# ESC_v0_2.net
KiCad netlist of a schematic drawn in EAGLE
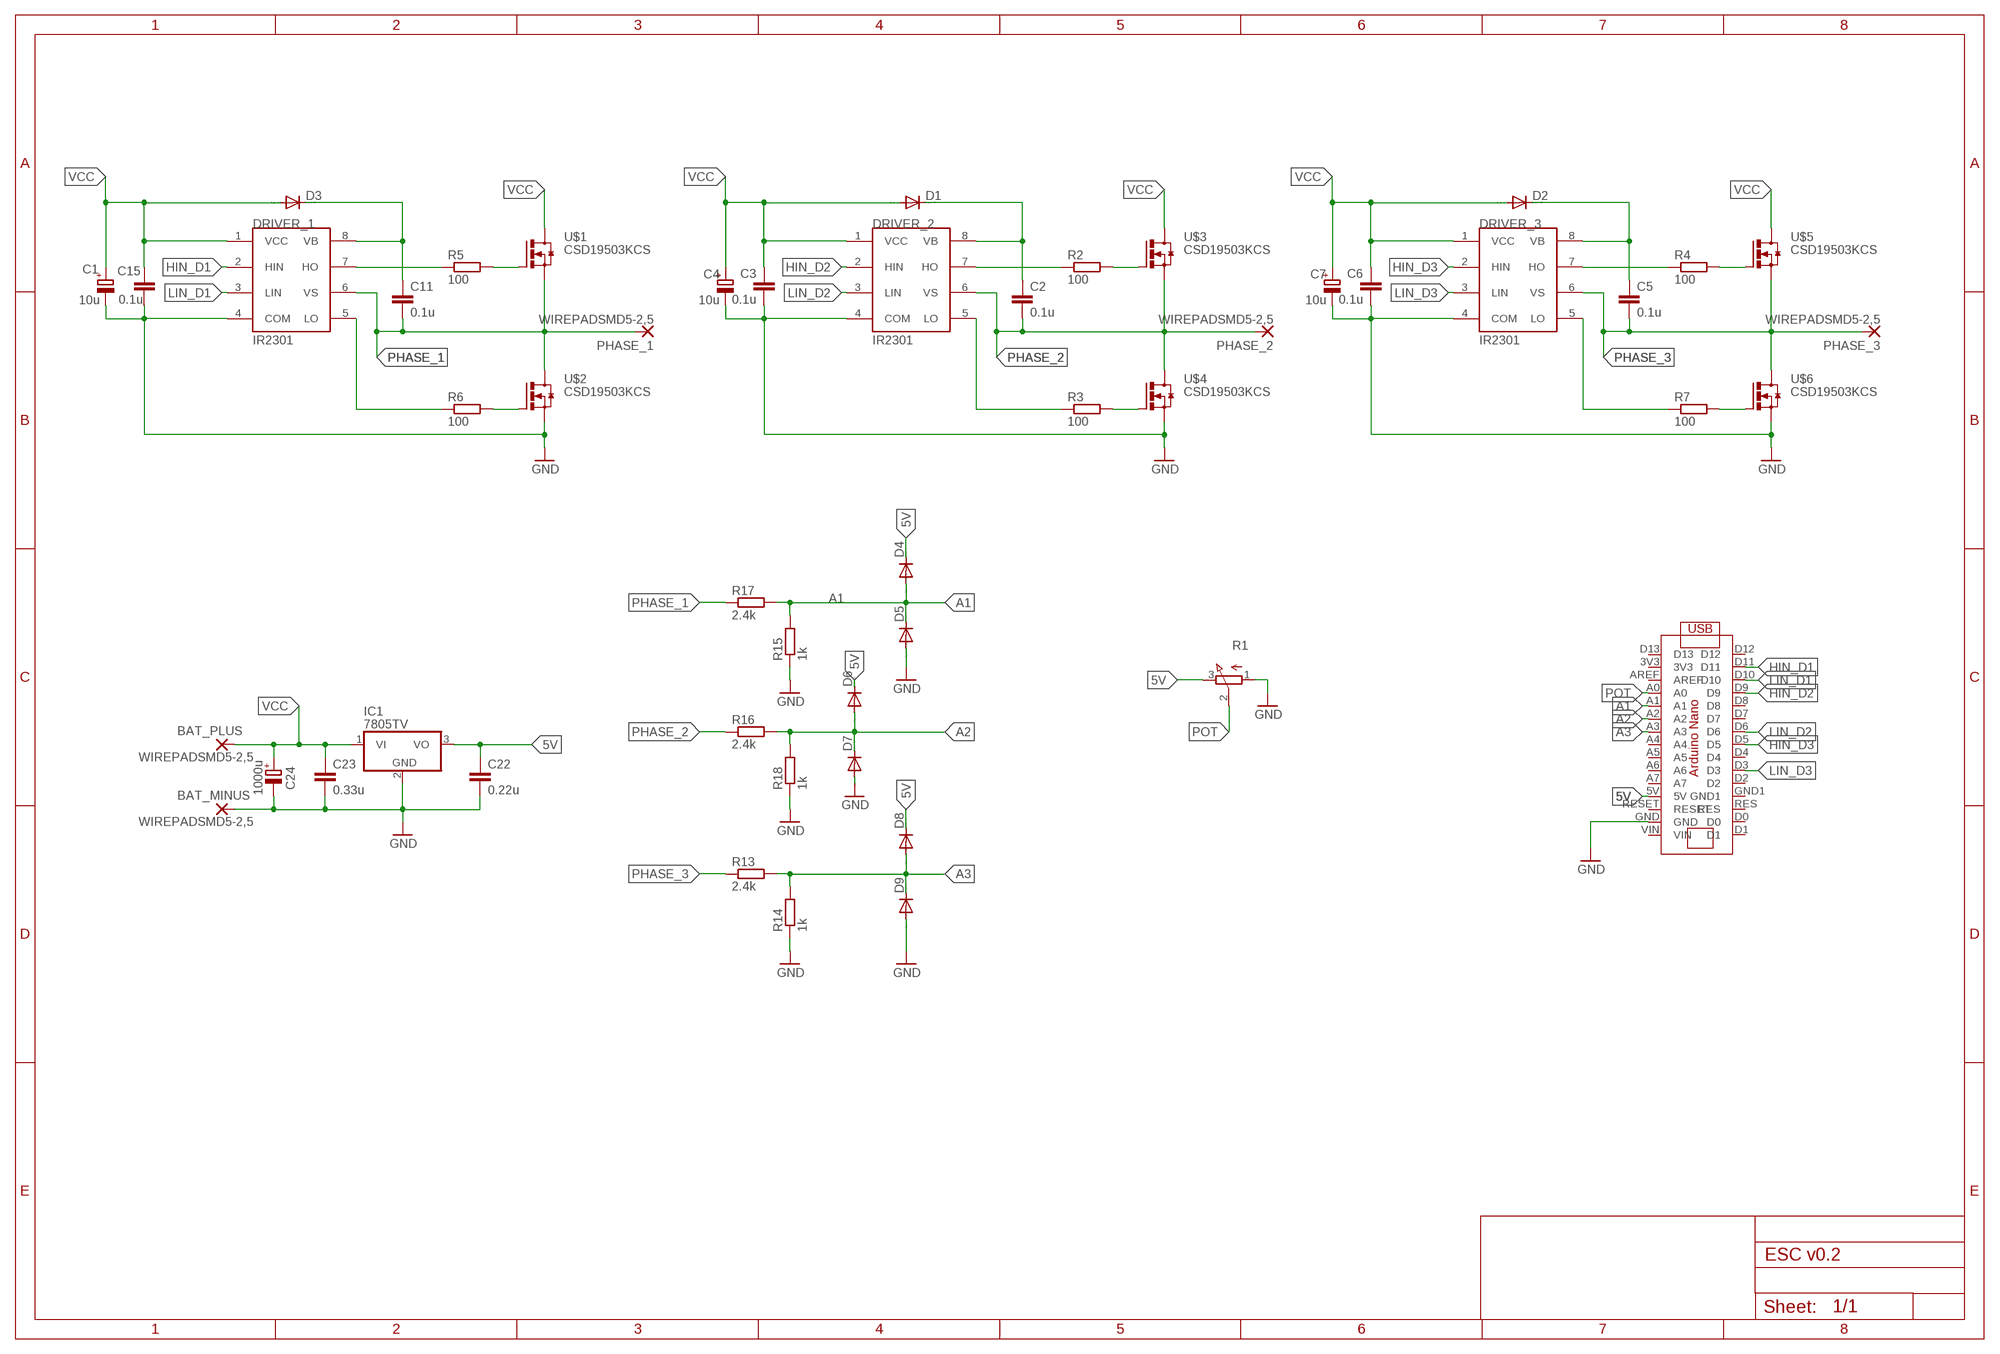
[diagram p0: schematic, sheet 1]

(export (version "E")
  (design (tool "Eeschema 10.0.6"))
  (components
    (comp (ref "BAT_MINUS")
      (value "WIREPADSMD5-2,5")
      (footprint "eagle-import:5-2,5")
      (libsource (lib "eagle-import") (part "WIREPADSMD5-2,5"))
    )
    (comp (ref "BAT_PLUS")
      (value "WIREPADSMD5-2,5")
      (footprint "eagle-import:5-2,5")
      (libsource (lib "eagle-import") (part "WIREPADSMD5-2,5"))
    )
    (comp (ref "C1")
      (value "10u")
      (footprint "eagle-import:153CLV-0605")
      (libsource (lib "eagle-import") (part "CPOL-EU153CLV-0605"))
    )
    (comp (ref "C2")
      (value "0.1u")
      (footprint "eagle-import:C1206")
      (libsource (lib "eagle-import") (part "CC1206"))
    )
    (comp (ref "C3")
      (value "0.1u")
      (footprint "eagle-import:C1206")
      (libsource (lib "eagle-import") (part "CC1206"))
    )
    (comp (ref "C4")
      (value "10u")
      (footprint "eagle-import:153CLV-0605")
      (libsource (lib "eagle-import") (part "CPOL-EU153CLV-0605"))
    )
    (comp (ref "C5")
      (value "0.1u")
      (footprint "eagle-import:C1206")
      (libsource (lib "eagle-import") (part "CC1206"))
    )
    (comp (ref "C6")
      (value "0.1u")
      (footprint "eagle-import:C1206")
      (libsource (lib "eagle-import") (part "CC1206"))
    )
    (comp (ref "C7")
      (value "10u")
      (footprint "eagle-import:153CLV-0605")
      (libsource (lib "eagle-import") (part "CPOL-EU153CLV-0605"))
    )
    (comp (ref "C11")
      (value "0.1u")
      (footprint "eagle-import:C1206")
      (libsource (lib "eagle-import") (part "CC1206"))
    )
    (comp (ref "C15")
      (value "0.1u")
      (footprint "eagle-import:C1206")
      (libsource (lib "eagle-import") (part "CC1206"))
    )
    (comp (ref "C22")
      (value "0.22u")
      (footprint "eagle-import:C1206")
      (libsource (lib "eagle-import") (part "CC1206"))
    )
    (comp (ref "C23")
      (value "0.33u")
      (footprint "eagle-import:C1206")
      (libsource (lib "eagle-import") (part "CC1206"))
    )
    (comp (ref "C24")
      (value "1000u")
      (footprint "eagle-import:E7,5-16")
      (libsource (lib "eagle-import") (part "CPOL-EUE7.5-16"))
    )
    (comp (ref "D1")
      (value "DIODE-DO41-10")
      (footprint "eagle-import:DO41-10")
      (libsource (lib "eagle-import") (part "DIODE-DO41-10"))
    )
    (comp (ref "D2")
      (value "DIODE-DO41-10")
      (footprint "eagle-import:DO41-10")
      (libsource (lib "eagle-import") (part "DIODE-DO41-10"))
    )
    (comp (ref "D3")
      (value "DIODE-DO41-10")
      (footprint "eagle-import:DO41-10")
      (libsource (lib "eagle-import") (part "DIODE-DO41-10"))
    )
    (comp (ref "D4")
      (value "DIODE-DO41-10")
      (footprint "eagle-import:DO41-10")
      (libsource (lib "eagle-import") (part "DIODE-DO41-10"))
    )
    (comp (ref "D5")
      (value "DIODE-DO41-10")
      (footprint "eagle-import:DO41-10")
      (libsource (lib "eagle-import") (part "DIODE-DO41-10"))
    )
    (comp (ref "D6")
      (value "DIODE-DO41-10")
      (footprint "eagle-import:DO41-10")
      (libsource (lib "eagle-import") (part "DIODE-DO41-10"))
    )
    (comp (ref "D7")
      (value "DIODE-DO41-10")
      (footprint "eagle-import:DO41-10")
      (libsource (lib "eagle-import") (part "DIODE-DO41-10"))
    )
    (comp (ref "D8")
      (value "DIODE-DO41-10")
      (footprint "eagle-import:DO41-10")
      (libsource (lib "eagle-import") (part "DIODE-DO41-10"))
    )
    (comp (ref "D9")
      (value "DIODE-DO41-10")
      (footprint "eagle-import:DO41-10")
      (libsource (lib "eagle-import") (part "DIODE-DO41-10"))
    )
    (comp (ref "DRIVER_1")
      (value "IR2301")
      (footprint "eagle-import:DIL08")
      (fields (field (name "MF") "Infineon"))
      (libsource (lib "eagle-import") (part "IR2301"))
    )
    (comp (ref "DRIVER_2")
      (value "IR2301")
      (footprint "eagle-import:DIL08")
      (fields (field (name "MF") "Infineon"))
      (libsource (lib "eagle-import") (part "IR2301"))
    )
    (comp (ref "DRIVER_3")
      (value "IR2301")
      (footprint "eagle-import:DIL08")
      (fields (field (name "MF") "Infineon"))
      (libsource (lib "eagle-import") (part "IR2301"))
    )
    (comp (ref "IC1")
      (value "7805TV")
      (footprint "eagle-import:TO220V")
      (libsource (lib "eagle-import") (part "78TV05"))
    )
    (comp (ref "PHASE_1")
      (value "WIREPADSMD5-2,5")
      (footprint "eagle-import:5-2,5")
      (libsource (lib "eagle-import") (part "WIREPADSMD5-2,5"))
    )
    (comp (ref "PHASE_2")
      (value "WIREPADSMD5-2,5")
      (footprint "eagle-import:5-2,5")
      (libsource (lib "eagle-import") (part "WIREPADSMD5-2,5"))
    )
    (comp (ref "PHASE_3")
      (value "WIREPADSMD5-2,5")
      (footprint "eagle-import:5-2,5")
      (libsource (lib "eagle-import") (part "WIREPADSMD5-2,5"))
    )
    (comp (ref "R1")
      (value "3RP/1610N")
      (footprint "eagle-import:3RP_1610N")
      (libsource (lib "eagle-import") (part "3RP/1610N"))
    )
    (comp (ref "R2")
      (value "100")
      (footprint "eagle-import:R1206")
      (libsource (lib "eagle-import") (part "R-EU_R1206"))
    )
    (comp (ref "R3")
      (value "100")
      (footprint "eagle-import:R1206")
      (libsource (lib "eagle-import") (part "R-EU_R1206"))
    )
    (comp (ref "R4")
      (value "100")
      (footprint "eagle-import:R1206")
      (libsource (lib "eagle-import") (part "R-EU_R1206"))
    )
    (comp (ref "R5")
      (value "100")
      (footprint "eagle-import:R1206")
      (libsource (lib "eagle-import") (part "R-EU_R1206"))
    )
    (comp (ref "R6")
      (value "100")
      (footprint "eagle-import:R1206")
      (libsource (lib "eagle-import") (part "R-EU_R1206"))
    )
    (comp (ref "R7")
      (value "100")
      (footprint "eagle-import:R1206")
      (libsource (lib "eagle-import") (part "R-EU_R1206"))
    )
    (comp (ref "R13")
      (value "2.4k")
      (footprint "eagle-import:R1206")
      (libsource (lib "eagle-import") (part "R-EU_R1206"))
    )
    (comp (ref "R14")
      (value "1k")
      (footprint "eagle-import:R1206")
      (libsource (lib "eagle-import") (part "R-EU_R1206"))
    )
    (comp (ref "R15")
      (value "1k")
      (footprint "eagle-import:R1206")
      (libsource (lib "eagle-import") (part "R-EU_R1206"))
    )
    (comp (ref "R16")
      (value "2.4k")
      (footprint "eagle-import:R1206")
      (libsource (lib "eagle-import") (part "R-EU_R1206"))
    )
    (comp (ref "R17")
      (value "2.4k")
      (footprint "eagle-import:R1206")
      (libsource (lib "eagle-import") (part "R-EU_R1206"))
    )
    (comp (ref "R18")
      (value "1k")
      (footprint "eagle-import:R1206")
      (libsource (lib "eagle-import") (part "R-EU_R1206"))
    )
    (comp (ref "U$1")
      (value "CSD19503KCS")
      (footprint "eagle-import:TO220BV")
      (fields (field (name "SPICEPREFIX") "M"))
      (libsource (lib "eagle-import") (part "CSD19503KCS"))
    )
    (comp (ref "U$2")
      (value "CSD19503KCS")
      (footprint "eagle-import:TO220BV")
      (libsource (lib "eagle-import") (part "CSD19503KCS"))
    )
    (comp (ref "U$3")
      (value "CSD19503KCS")
      (footprint "eagle-import:TO220BV")
      (libsource (lib "eagle-import") (part "CSD19503KCS"))
    )
    (comp (ref "U$4")
      (value "CSD19503KCS")
      (footprint "eagle-import:TO220BV")
      (libsource (lib "eagle-import") (part "CSD19503KCS"))
    )
    (comp (ref "U$5")
      (value "CSD19503KCS")
      (footprint "eagle-import:TO220BV")
      (libsource (lib "eagle-import") (part "CSD19503KCS"))
    )
    (comp (ref "U$6")
      (value "CSD19503KCS")
      (footprint "eagle-import:TO220BV")
      (libsource (lib "eagle-import") (part "CSD19503KCS"))
    )
    (comp (ref "U$7")
      (value "ARDUINO-NANO")
      (footprint "eagle-import:ARDUINO-NANO")
      (libsource (lib "eagle-import") (part "ARDUINO-NANO"))
    )
  )
  (nets
    (net (code "1") (name "/VB") (class "Default")
      (node (ref "C11") (pin "1") (pinfunction "1_1") (pintype "passive"))
      (node (ref "C2") (pin "1") (pinfunction "1_1") (pintype "passive"))
      (node (ref "C5") (pin "1") (pinfunction "1_1") (pintype "passive"))
      (node (ref "D1") (pin "C") (pinfunction "C_C") (pintype "passive"))
      (node (ref "D2") (pin "C") (pinfunction "C_C") (pintype "passive"))
      (node (ref "D3") (pin "C") (pinfunction "C_C") (pintype "passive"))
      (node (ref "DRIVER_1") (pin "8") (pinfunction "VB_8") (pintype "power_in"))
      (node (ref "DRIVER_2") (pin "8") (pinfunction "VB_8") (pintype "power_in"))
      (node (ref "DRIVER_3") (pin "8") (pinfunction "VB_8") (pintype "power_in"))
    )
    (net (code "2") (name "5V") (class "Default")
      (node (ref "C22") (pin "1") (pinfunction "1_1") (pintype "passive"))
      (node (ref "D4") (pin "C") (pinfunction "C_C") (pintype "passive"))
      (node (ref "D6") (pin "C") (pinfunction "C_C") (pintype "passive"))
      (node (ref "D8") (pin "C") (pinfunction "C_C") (pintype "passive"))
      (node (ref "IC1") (pin "3") (pinfunction "VO_3") (pintype "passive"))
      (node (ref "R1") (pin "3") (pinfunction "E_3") (pintype "passive"))
      (node (ref "U$7") (pin "5V") (pinfunction "5V_5V") (pintype "bidirectional"))
    )
    (net (code "3") (name "A1") (class "Default")
      (node (ref "D4") (pin "A") (pinfunction "A_A") (pintype "passive"))
      (node (ref "D5") (pin "C") (pinfunction "C_C") (pintype "passive"))
      (node (ref "R15") (pin "2") (pinfunction "2_2") (pintype "bidirectional"))
      (node (ref "R17") (pin "2") (pinfunction "2_2") (pintype "bidirectional"))
      (node (ref "U$7") (pin "A1") (pinfunction "A1_A1") (pintype "bidirectional"))
    )
    (net (code "4") (name "A2") (class "Default")
      (node (ref "D6") (pin "A") (pinfunction "A_A") (pintype "passive"))
      (node (ref "D7") (pin "C") (pinfunction "C_C") (pintype "passive"))
      (node (ref "R16") (pin "2") (pinfunction "2_2") (pintype "bidirectional"))
      (node (ref "R18") (pin "2") (pinfunction "2_2") (pintype "bidirectional"))
      (node (ref "U$7") (pin "A2") (pinfunction "A2_A2") (pintype "bidirectional"))
    )
    (net (code "5") (name "A3") (class "Default")
      (node (ref "D8") (pin "A") (pinfunction "A_A") (pintype "passive"))
      (node (ref "D9") (pin "C") (pinfunction "C_C") (pintype "passive"))
      (node (ref "R13") (pin "2") (pinfunction "2_2") (pintype "bidirectional"))
      (node (ref "R14") (pin "2") (pinfunction "2_2") (pintype "bidirectional"))
      (node (ref "U$7") (pin "A3") (pinfunction "A3_A3") (pintype "bidirectional"))
    )
    (net (code "6") (name "GND") (class "Default")
      (node (ref "BAT_MINUS") (pin "1") (pinfunction "P_1") (pintype "passive"))
      (node (ref "C1") (pin "-") (pinfunction "-_-") (pintype "passive"))
      (node (ref "C15") (pin "2") (pinfunction "2_2") (pintype "passive"))
      (node (ref "C22") (pin "2") (pinfunction "2_2") (pintype "passive"))
      (node (ref "C23") (pin "2") (pinfunction "2_2") (pintype "passive"))
      (node (ref "C24") (pin "-") (pinfunction "-_-") (pintype "passive"))
      (node (ref "C3") (pin "2") (pinfunction "2_2") (pintype "passive"))
      (node (ref "C4") (pin "-") (pinfunction "-_-") (pintype "passive"))
      (node (ref "C6") (pin "2") (pinfunction "2_2") (pintype "passive"))
      (node (ref "C7") (pin "-") (pinfunction "-_-") (pintype "passive"))
      (node (ref "D5") (pin "A") (pinfunction "A_A") (pintype "passive"))
      (node (ref "D7") (pin "A") (pinfunction "A_A") (pintype "passive"))
      (node (ref "D9") (pin "A") (pinfunction "A_A") (pintype "passive"))
      (node (ref "DRIVER_1") (pin "4") (pinfunction "COM_4") (pintype "power_in"))
      (node (ref "DRIVER_2") (pin "4") (pinfunction "COM_4") (pintype "power_in"))
      (node (ref "DRIVER_3") (pin "4") (pinfunction "COM_4") (pintype "power_in"))
      (node (ref "IC1") (pin "2") (pinfunction "GND_2") (pintype "passive"))
      (node (ref "R1") (pin "1") (pinfunction "A_1") (pintype "passive"))
      (node (ref "R14") (pin "1") (pinfunction "1_1") (pintype "bidirectional"))
      (node (ref "R15") (pin "1") (pinfunction "1_1") (pintype "bidirectional"))
      (node (ref "R18") (pin "1") (pinfunction "1_1") (pintype "bidirectional"))
      (node (ref "U$2") (pin "S") (pinfunction "S_S") (pintype "passive"))
      (node (ref "U$4") (pin "S") (pinfunction "S_S") (pintype "passive"))
      (node (ref "U$6") (pin "S") (pinfunction "S_S") (pintype "passive"))
      (node (ref "U$7") (pin "GND") (pinfunction "GND_GND") (pintype "bidirectional"))
    )
    (net (code "7") (name "HIN_D1") (class "Default")
      (node (ref "DRIVER_1") (pin "2") (pinfunction "HIN_2") (pintype "input"))
      (node (ref "U$7") (pin "D11") (pinfunction "D11_D11") (pintype "bidirectional"))
    )
    (net (code "8") (name "HIN_D2") (class "Default")
      (node (ref "DRIVER_2") (pin "2") (pinfunction "HIN_2") (pintype "input"))
      (node (ref "U$7") (pin "D9") (pinfunction "D9_D9") (pintype "bidirectional"))
    )
    (net (code "9") (name "HIN_D3") (class "Default")
      (node (ref "DRIVER_3") (pin "2") (pinfunction "HIN_2") (pintype "input"))
      (node (ref "U$7") (pin "D5") (pinfunction "D5_D5") (pintype "bidirectional"))
    )
    (net (code "10") (name "LIN_D1") (class "Default")
      (node (ref "DRIVER_1") (pin "3") (pinfunction "LIN_3") (pintype "input"))
      (node (ref "U$7") (pin "D10") (pinfunction "D10_D10") (pintype "bidirectional"))
    )
    (net (code "11") (name "LIN_D2") (class "Default")
      (node (ref "DRIVER_2") (pin "3") (pinfunction "LIN_3") (pintype "input"))
      (node (ref "U$7") (pin "D6") (pinfunction "D6_D6") (pintype "bidirectional"))
    )
    (net (code "12") (name "LIN_D3") (class "Default")
      (node (ref "DRIVER_3") (pin "3") (pinfunction "LIN_3") (pintype "input"))
      (node (ref "U$7") (pin "D3") (pinfunction "D3_D3") (pintype "bidirectional"))
    )
    (net (code "13") (name "Net-(DRIVER_1-HO)") (class "Default")
      (node (ref "DRIVER_1") (pin "7") (pinfunction "HO_7") (pintype "output"))
      (node (ref "R5") (pin "1") (pinfunction "1_1") (pintype "bidirectional"))
    )
    (net (code "14") (name "Net-(DRIVER_1-LO)") (class "Default")
      (node (ref "DRIVER_1") (pin "5") (pinfunction "LO_5") (pintype "output"))
      (node (ref "R6") (pin "1") (pinfunction "1_1") (pintype "bidirectional"))
    )
    (net (code "15") (name "Net-(DRIVER_2-HO)") (class "Default")
      (node (ref "DRIVER_2") (pin "7") (pinfunction "HO_7") (pintype "output"))
      (node (ref "R2") (pin "1") (pinfunction "1_1") (pintype "bidirectional"))
    )
    (net (code "16") (name "Net-(DRIVER_2-LO)") (class "Default")
      (node (ref "DRIVER_2") (pin "5") (pinfunction "LO_5") (pintype "output"))
      (node (ref "R3") (pin "1") (pinfunction "1_1") (pintype "bidirectional"))
    )
    (net (code "17") (name "Net-(DRIVER_3-HO)") (class "Default")
      (node (ref "DRIVER_3") (pin "7") (pinfunction "HO_7") (pintype "output"))
      (node (ref "R4") (pin "1") (pinfunction "1_1") (pintype "bidirectional"))
    )
    (net (code "18") (name "Net-(DRIVER_3-LO)") (class "Default")
      (node (ref "DRIVER_3") (pin "5") (pinfunction "LO_5") (pintype "output"))
      (node (ref "R7") (pin "1") (pinfunction "1_1") (pintype "bidirectional"))
    )
    (net (code "19") (name "Net-(R2-Pad2)") (class "Default")
      (node (ref "R2") (pin "2") (pinfunction "2_2") (pintype "bidirectional"))
      (node (ref "U$3") (pin "G") (pinfunction "G_G") (pintype "passive"))
    )
    (net (code "20") (name "Net-(R3-Pad2)") (class "Default")
      (node (ref "R3") (pin "2") (pinfunction "2_2") (pintype "bidirectional"))
      (node (ref "U$4") (pin "G") (pinfunction "G_G") (pintype "passive"))
    )
    (net (code "21") (name "Net-(R4-Pad2)") (class "Default")
      (node (ref "R4") (pin "2") (pinfunction "2_2") (pintype "bidirectional"))
      (node (ref "U$5") (pin "G") (pinfunction "G_G") (pintype "passive"))
    )
    (net (code "22") (name "Net-(R5-Pad2)") (class "Default")
      (node (ref "R5") (pin "2") (pinfunction "2_2") (pintype "bidirectional"))
      (node (ref "U$1") (pin "G") (pinfunction "G_G") (pintype "passive"))
    )
    (net (code "23") (name "Net-(R6-Pad2)") (class "Default")
      (node (ref "R6") (pin "2") (pinfunction "2_2") (pintype "bidirectional"))
      (node (ref "U$2") (pin "G") (pinfunction "G_G") (pintype "passive"))
    )
    (net (code "24") (name "Net-(R7-Pad2)") (class "Default")
      (node (ref "R7") (pin "2") (pinfunction "2_2") (pintype "bidirectional"))
      (node (ref "U$6") (pin "G") (pinfunction "G_G") (pintype "passive"))
    )
    (net (code "25") (name "PHASE_1") (class "Default")
      (node (ref "C11") (pin "2") (pinfunction "2_2") (pintype "passive"))
      (node (ref "DRIVER_1") (pin "6") (pinfunction "VS_6") (pintype "output"))
      (node (ref "PHASE_1") (pin "1") (pinfunction "P_1") (pintype "passive"))
      (node (ref "R17") (pin "1") (pinfunction "1_1") (pintype "bidirectional"))
      (node (ref "U$1") (pin "S") (pinfunction "S_S") (pintype "passive"))
      (node (ref "U$2") (pin "D") (pinfunction "D_D") (pintype "passive"))
    )
    (net (code "26") (name "PHASE_2") (class "Default")
      (node (ref "C2") (pin "2") (pinfunction "2_2") (pintype "passive"))
      (node (ref "DRIVER_2") (pin "6") (pinfunction "VS_6") (pintype "output"))
      (node (ref "PHASE_2") (pin "1") (pinfunction "P_1") (pintype "passive"))
      (node (ref "R16") (pin "1") (pinfunction "1_1") (pintype "bidirectional"))
      (node (ref "U$3") (pin "S") (pinfunction "S_S") (pintype "passive"))
      (node (ref "U$4") (pin "D") (pinfunction "D_D") (pintype "passive"))
    )
    (net (code "27") (name "PHASE_3") (class "Default")
      (node (ref "C5") (pin "2") (pinfunction "2_2") (pintype "passive"))
      (node (ref "DRIVER_3") (pin "6") (pinfunction "VS_6") (pintype "output"))
      (node (ref "PHASE_3") (pin "1") (pinfunction "P_1") (pintype "passive"))
      (node (ref "R13") (pin "1") (pinfunction "1_1") (pintype "bidirectional"))
      (node (ref "U$5") (pin "S") (pinfunction "S_S") (pintype "passive"))
      (node (ref "U$6") (pin "D") (pinfunction "D_D") (pintype "passive"))
    )
    (net (code "28") (name "POT") (class "Default")
      (node (ref "R1") (pin "2") (pinfunction "S_2") (pintype "passive"))
      (node (ref "U$7") (pin "A0") (pinfunction "A0_A0") (pintype "bidirectional"))
    )
    (net (code "29") (name "VCC") (class "Default")
      (node (ref "BAT_PLUS") (pin "1") (pinfunction "P_1") (pintype "passive"))
      (node (ref "C1") (pin "+") (pinfunction "+_+") (pintype "passive"))
      (node (ref "C15") (pin "1") (pinfunction "1_1") (pintype "passive"))
      (node (ref "C23") (pin "1") (pinfunction "1_1") (pintype "passive"))
      (node (ref "C24") (pin "+") (pinfunction "+_+") (pintype "passive"))
      (node (ref "C3") (pin "1") (pinfunction "1_1") (pintype "passive"))
      (node (ref "C4") (pin "+") (pinfunction "+_+") (pintype "passive"))
      (node (ref "C6") (pin "1") (pinfunction "1_1") (pintype "passive"))
      (node (ref "C7") (pin "+") (pinfunction "+_+") (pintype "passive"))
      (node (ref "D1") (pin "A") (pinfunction "A_A") (pintype "passive"))
      (node (ref "D2") (pin "A") (pinfunction "A_A") (pintype "passive"))
      (node (ref "D3") (pin "A") (pinfunction "A_A") (pintype "passive"))
      (node (ref "DRIVER_1") (pin "1") (pinfunction "VCC_1") (pintype "power_in"))
      (node (ref "DRIVER_2") (pin "1") (pinfunction "VCC_1") (pintype "power_in"))
      (node (ref "DRIVER_3") (pin "1") (pinfunction "VCC_1") (pintype "power_in"))
      (node (ref "IC1") (pin "1") (pinfunction "VI_1") (pintype "input"))
      (node (ref "U$1") (pin "D") (pinfunction "D_D") (pintype "passive"))
      (node (ref "U$3") (pin "D") (pinfunction "D_D") (pintype "passive"))
      (node (ref "U$5") (pin "D") (pinfunction "D_D") (pintype "passive"))
    )
    (net (code "30") (name "unconnected-(U$7-Pad3V3)") (class "Default")
      (node (ref "U$7") (pin "3V3") (pinfunction "3V3_3V3") (pintype "bidirectional"))
    )
    (net (code "31") (name "unconnected-(U$7-PadA4)") (class "Default")
      (node (ref "U$7") (pin "A4") (pinfunction "A4_A4") (pintype "bidirectional"))
    )
    (net (code "32") (name "unconnected-(U$7-PadA5)") (class "Default")
      (node (ref "U$7") (pin "A5") (pinfunction "A5_A5") (pintype "bidirectional"))
    )
    (net (code "33") (name "unconnected-(U$7-PadA6)") (class "Default")
      (node (ref "U$7") (pin "A6") (pinfunction "A6_A6") (pintype "bidirectional"))
    )
    (net (code "34") (name "unconnected-(U$7-PadA7)") (class "Default")
      (node (ref "U$7") (pin "A7") (pinfunction "A7_A7") (pintype "bidirectional"))
    )
    (net (code "35") (name "unconnected-(U$7-PadAREF)") (class "Default")
      (node (ref "U$7") (pin "AREF") (pinfunction "AREF_AREF") (pintype "bidirectional"))
    )
    (net (code "36") (name "unconnected-(U$7-PadD0)") (class "Default")
      (node (ref "U$7") (pin "D0") (pinfunction "D0_D0") (pintype "bidirectional"))
    )
    (net (code "37") (name "unconnected-(U$7-PadD1)") (class "Default")
      (node (ref "U$7") (pin "D1") (pinfunction "D1_D1") (pintype "bidirectional"))
    )
    (net (code "38") (name "unconnected-(U$7-PadD2)") (class "Default")
      (node (ref "U$7") (pin "D2") (pinfunction "D2_D2") (pintype "bidirectional"))
    )
    (net (code "39") (name "unconnected-(U$7-PadD4)") (class "Default")
      (node (ref "U$7") (pin "D4") (pinfunction "D4_D4") (pintype "bidirectional"))
    )
    (net (code "40") (name "unconnected-(U$7-PadD7)") (class "Default")
      (node (ref "U$7") (pin "D7") (pinfunction "D7_D7") (pintype "bidirectional"))
    )
    (net (code "41") (name "unconnected-(U$7-PadD8)") (class "Default")
      (node (ref "U$7") (pin "D8") (pinfunction "D8_D8") (pintype "bidirectional"))
    )
    (net (code "42") (name "unconnected-(U$7-PadD12)") (class "Default")
      (node (ref "U$7") (pin "D12") (pinfunction "D12_D12") (pintype "bidirectional"))
    )
    (net (code "43") (name "unconnected-(U$7-PadD13)") (class "Default")
      (node (ref "U$7") (pin "D13") (pinfunction "D13_D13") (pintype "bidirectional"))
    )
    (net (code "44") (name "unconnected-(U$7-PadGND1)") (class "Default")
      (node (ref "U$7") (pin "GND1") (pinfunction "GND1_GND1") (pintype "bidirectional"))
    )
    (net (code "45") (name "unconnected-(U$7-PadRES)") (class "Default")
      (node (ref "U$7") (pin "RES") (pinfunction "RES_RES") (pintype "bidirectional"))
    )
    (net (code "46") (name "unconnected-(U$7-PadRESET)") (class "Default")
      (node (ref "U$7") (pin "RESET") (pinfunction "RESET_RESET") (pintype "bidirectional"))
    )
    (net (code "47") (name "unconnected-(U$7-PadVIN)") (class "Default")
      (node (ref "U$7") (pin "VIN") (pinfunction "VIN_VIN") (pintype "bidirectional"))
    )
  )
)
